# e-programmer-alt.net
KiCad netlist of a schematic drawn in EAGLE
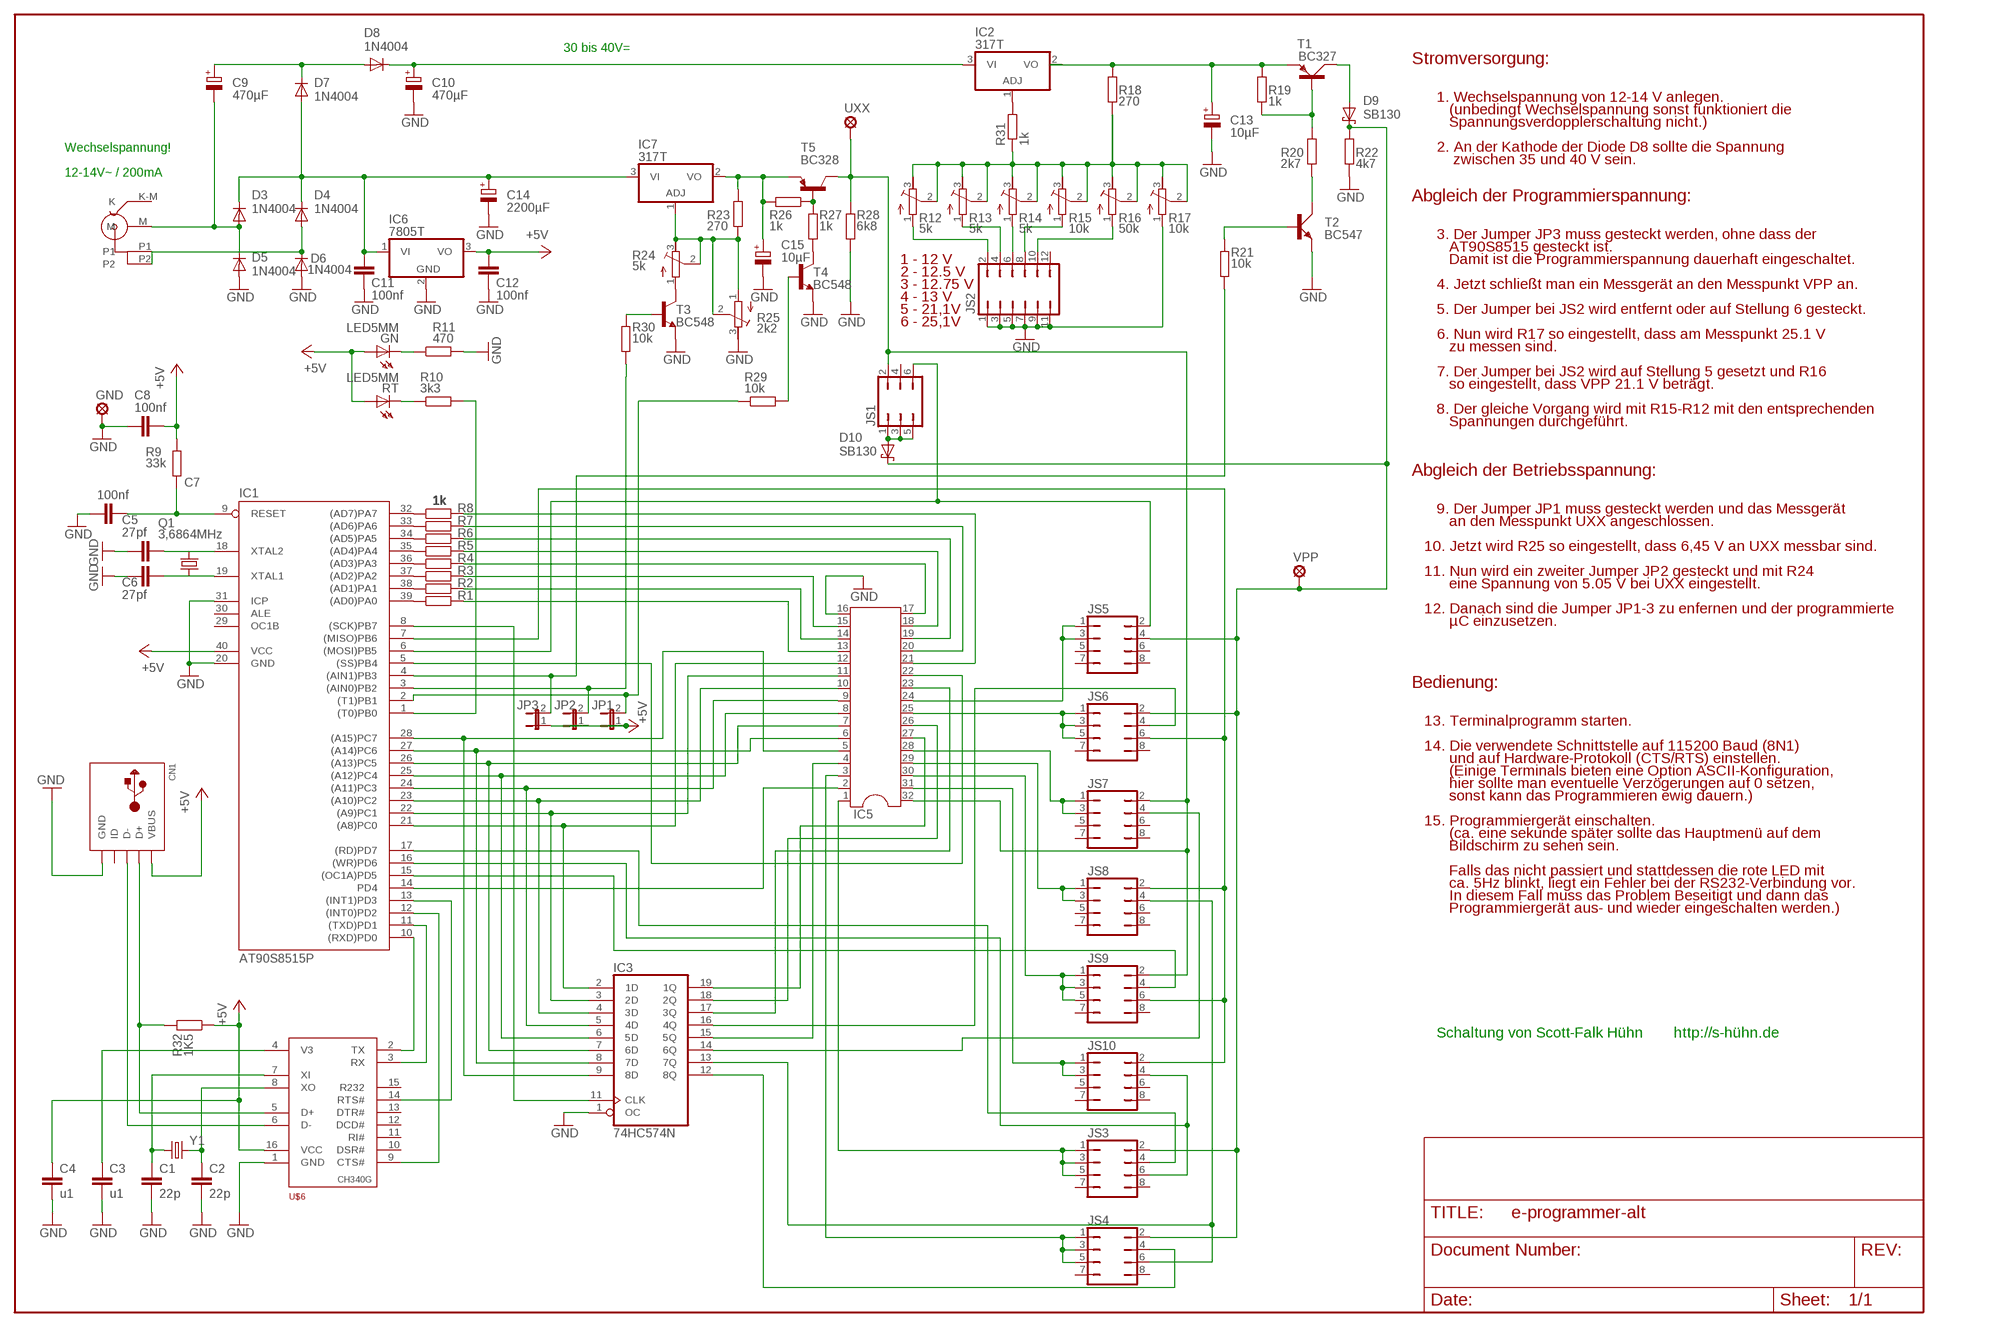
[diagram p0: schematic, sheet 1]

(export (version "E")
  (design (tool "Eeschema 10.0.6"))
  (components
    (comp (ref "BU1")
      (value "KLIN_BU")
      (footprint "eagle-import:KLIN_BU")
      (libsource (lib "eagle-import") (part "KLIN_BU"))
    )
    (comp (ref "C1")
      (value "22p")
      (footprint "eagle-import:C025-025X050")
      (libsource (lib "eagle-import") (part "C-EU025-025X050"))
    )
    (comp (ref "C2")
      (value "22p")
      (footprint "eagle-import:C025-025X050")
      (libsource (lib "eagle-import") (part "C-EU025-025X050"))
    )
    (comp (ref "C3")
      (value "u1")
      (footprint "eagle-import:C025-025X050")
      (libsource (lib "eagle-import") (part "C-EU025-025X050"))
    )
    (comp (ref "C4")
      (value "u1")
      (footprint "eagle-import:C025-025X050")
      (libsource (lib "eagle-import") (part "C-EU025-025X050"))
    )
    (comp (ref "C5")
      (value "27pf")
      (footprint "eagle-import:C025-024X044")
      (libsource (lib "eagle-import") (part "C-EU025-024X044"))
    )
    (comp (ref "C6")
      (value "27pf")
      (footprint "eagle-import:C025-024X044")
      (libsource (lib "eagle-import") (part "C-EU025-024X044"))
    )
    (comp (ref "C7")
      (value "100nf")
      (footprint "eagle-import:C025-024X044")
      (libsource (lib "eagle-import") (part "C-EU025-024X044"))
    )
    (comp (ref "C8")
      (value "100nf")
      (footprint "eagle-import:C025-024X044")
      (libsource (lib "eagle-import") (part "C-EU025-024X044"))
    )
    (comp (ref "C9")
      (value "470µF")
      (footprint "eagle-import:E3,5-10")
      (libsource (lib "eagle-import") (part "CPOL-EUE3.5-10"))
    )
    (comp (ref "C10")
      (value "470µF")
      (footprint "eagle-import:E5-13")
      (libsource (lib "eagle-import") (part "CPOL-EUE5-13"))
    )
    (comp (ref "C11")
      (value "100nf")
      (footprint "eagle-import:C025-024X044")
      (libsource (lib "eagle-import") (part "C-EU025-024X044"))
    )
    (comp (ref "C12")
      (value "100nf")
      (footprint "eagle-import:C025-024X044")
      (libsource (lib "eagle-import") (part "C-EU025-024X044"))
    )
    (comp (ref "C13")
      (value "10µF")
      (footprint "eagle-import:E2,5-5")
      (libsource (lib "eagle-import") (part "CPOL-EUE2.5-5"))
    )
    (comp (ref "C14")
      (value "2200µF")
      (footprint "eagle-import:E7,5-16")
      (libsource (lib "eagle-import") (part "CPOL-EUE7.5-16"))
    )
    (comp (ref "C15")
      (value "10µF")
      (footprint "eagle-import:E5-5")
      (libsource (lib "eagle-import") (part "CPOL-EUE5-5"))
    )
    (comp (ref "CN1")
      (value "USBTHM")
      (footprint "eagle-import:USB-MINIB-THM")
      (libsource (lib "eagle-import") (part "USBTHM"))
    )
    (comp (ref "D3")
      (value "1N4004")
      (footprint "eagle-import:DO41-10")
      (libsource (lib "eagle-import") (part "1N4004"))
    )
    (comp (ref "D4")
      (value "1N4004")
      (footprint "eagle-import:DO41-10")
      (libsource (lib "eagle-import") (part "1N4004"))
    )
    (comp (ref "D5")
      (value "1N4004")
      (footprint "eagle-import:DO41-10")
      (libsource (lib "eagle-import") (part "1N4004"))
    )
    (comp (ref "D6")
      (value "1N4004")
      (footprint "eagle-import:DO41-10")
      (libsource (lib "eagle-import") (part "1N4004"))
    )
    (comp (ref "D7")
      (value "1N4004")
      (footprint "eagle-import:DO41-10")
      (libsource (lib "eagle-import") (part "1N4004"))
    )
    (comp (ref "D8")
      (value "1N4004")
      (footprint "eagle-import:DO41-10")
      (libsource (lib "eagle-import") (part "1N4004"))
    )
    (comp (ref "D9")
      (value "SB130")
      (footprint "eagle-import:DO35-7")
      (libsource (lib "eagle-import") (part "SCHOTTKY-DIODEDO35-7"))
    )
    (comp (ref "D10")
      (value "SB130")
      (footprint "eagle-import:DO35-7")
      (libsource (lib "eagle-import") (part "SCHOTTKY-DIODEDO35-7"))
    )
    (comp (ref "GN")
      (value "LED5MM")
      (footprint "eagle-import:LED5MM")
      (libsource (lib "eagle-import") (part "LED5MM"))
    )
    (comp (ref "GND")
      (value "LSP10")
      (footprint "eagle-import:LSP10")
      (libsource (lib "eagle-import") (part "LSP10"))
    )
    (comp (ref "IC1")
      (value "AT90S8515P")
      (footprint "eagle-import:DIL40")
      (libsource (lib "eagle-import") (part "AT90S8515P"))
    )
    (comp (ref "IC2")
      (value "317T")
      (footprint "eagle-import:TO220H")
      (libsource (lib "eagle-import") (part "317T"))
    )
    (comp (ref "IC3")
      (value "74HC574N")
      (footprint "eagle-import:DIL20")
      (libsource (lib "eagle-import") (part "74574NHC"))
    )
    (comp (ref "IC5")
      (value "DIL32")
      (footprint "eagle-import:DIL32")
      (libsource (lib "eagle-import") (part "DIL32"))
    )
    (comp (ref "IC6")
      (value "7805T")
      (footprint "eagle-import:TO220H")
      (libsource (lib "eagle-import") (part "78T05"))
    )
    (comp (ref "IC7")
      (value "317T")
      (footprint "eagle-import:TO220H")
      (libsource (lib "eagle-import") (part "317T"))
    )
    (comp (ref "JP1")
      (value "JP1E")
      (footprint "eagle-import:JP1")
      (libsource (lib "eagle-import") (part "JP1E"))
    )
    (comp (ref "JP2")
      (value "JP1E")
      (footprint "eagle-import:JP1")
      (libsource (lib "eagle-import") (part "JP1E"))
    )
    (comp (ref "JP3")
      (value "JP1E")
      (footprint "eagle-import:JP1")
      (libsource (lib "eagle-import") (part "JP1E"))
    )
    (comp (ref "JS1")
      (value "JP3Q")
      (footprint "eagle-import:JP3Q")
      (libsource (lib "eagle-import") (part "JP3Q"))
    )
    (comp (ref "JS2")
      (value "JP6Q")
      (footprint "eagle-import:JP6Q")
      (libsource (lib "eagle-import") (part "JP6Q"))
    )
    (comp (ref "JS3")
      (value "JP4Q")
      (footprint "eagle-import:JP4Q")
      (libsource (lib "eagle-import") (part "JP4Q"))
    )
    (comp (ref "JS4")
      (value "JP4Q")
      (footprint "eagle-import:JP4Q")
      (libsource (lib "eagle-import") (part "JP4Q"))
    )
    (comp (ref "JS5")
      (value "JP4Q")
      (footprint "eagle-import:JP4Q")
      (libsource (lib "eagle-import") (part "JP4Q"))
    )
    (comp (ref "JS6")
      (value "JP4Q")
      (footprint "eagle-import:JP4Q")
      (libsource (lib "eagle-import") (part "JP4Q"))
    )
    (comp (ref "JS7")
      (value "JP4Q")
      (footprint "eagle-import:JP4Q")
      (libsource (lib "eagle-import") (part "JP4Q"))
    )
    (comp (ref "JS8")
      (value "JP4Q")
      (footprint "eagle-import:JP4Q")
      (libsource (lib "eagle-import") (part "JP4Q"))
    )
    (comp (ref "JS9")
      (value "JP4Q")
      (footprint "eagle-import:JP4Q")
      (libsource (lib "eagle-import") (part "JP4Q"))
    )
    (comp (ref "JS10")
      (value "JP4Q")
      (footprint "eagle-import:JP4Q")
      (libsource (lib "eagle-import") (part "JP4Q"))
    )
    (comp (ref "Q1")
      (value "3,6864MHz")
      (footprint "eagle-import:HC49U-V")
      (libsource (lib "eagle-import") (part "HC49U-V"))
    )
    (comp (ref "R1")
      (value "1k")
      (footprint "eagle-import:0207_7")
      (libsource (lib "eagle-import") (part "R-EU_0207/7"))
    )
    (comp (ref "R2")
      (value "1k")
      (footprint "eagle-import:0207_7")
      (libsource (lib "eagle-import") (part "R-EU_0207/7"))
    )
    (comp (ref "R3")
      (value "1k")
      (footprint "eagle-import:0207_7")
      (libsource (lib "eagle-import") (part "R-EU_0207/7"))
    )
    (comp (ref "R4")
      (value "1k")
      (footprint "eagle-import:0207_7")
      (libsource (lib "eagle-import") (part "R-EU_0207/7"))
    )
    (comp (ref "R5")
      (value "1k")
      (footprint "eagle-import:0207_7")
      (libsource (lib "eagle-import") (part "R-EU_0207/7"))
    )
    (comp (ref "R6")
      (value "1k")
      (footprint "eagle-import:0207_7")
      (libsource (lib "eagle-import") (part "R-EU_0207/7"))
    )
    (comp (ref "R7")
      (value "1k")
      (footprint "eagle-import:0207_7")
      (libsource (lib "eagle-import") (part "R-EU_0207/7"))
    )
    (comp (ref "R8")
      (value "1k")
      (footprint "eagle-import:0207_7")
      (libsource (lib "eagle-import") (part "R-EU_0207/7"))
    )
    (comp (ref "R9")
      (value "33k")
      (footprint "eagle-import:0204_7")
      (libsource (lib "eagle-import") (part "R-EU_0204/7"))
    )
    (comp (ref "R10")
      (value "3k3")
      (footprint "eagle-import:0204_7")
      (libsource (lib "eagle-import") (part "R-EU_0204/7"))
    )
    (comp (ref "R11")
      (value "470")
      (footprint "eagle-import:0204_7")
      (libsource (lib "eagle-import") (part "R-EU_0204/7"))
    )
    (comp (ref "R12")
      (value "5k")
      (footprint "eagle-import:RTRIM3296Y")
      (libsource (lib "eagle-import") (part "R-TRIMM3296Y"))
    )
    (comp (ref "R13")
      (value "5k")
      (footprint "eagle-import:RTRIM3296Y")
      (libsource (lib "eagle-import") (part "R-TRIMM3296Y"))
    )
    (comp (ref "R14")
      (value "5k")
      (footprint "eagle-import:RTRIM3296Y")
      (libsource (lib "eagle-import") (part "R-TRIMM3296Y"))
    )
    (comp (ref "R15")
      (value "10k")
      (footprint "eagle-import:RTRIM3296Y")
      (libsource (lib "eagle-import") (part "R-TRIMM3296Y"))
    )
    (comp (ref "R16")
      (value "50k")
      (footprint "eagle-import:RTRIM3296Y")
      (libsource (lib "eagle-import") (part "R-TRIMM3296Y"))
    )
    (comp (ref "R17")
      (value "10k")
      (footprint "eagle-import:RTRIM3296Y")
      (libsource (lib "eagle-import") (part "R-TRIMM3296Y"))
    )
    (comp (ref "R18")
      (value "270")
      (footprint "eagle-import:0207_7")
      (libsource (lib "eagle-import") (part "R-EU_0207/7"))
    )
    (comp (ref "R19")
      (value "1k")
      (footprint "eagle-import:0207_7")
      (libsource (lib "eagle-import") (part "R-EU_0207/7"))
    )
    (comp (ref "R20")
      (value "2k7")
      (footprint "eagle-import:0207_7")
      (libsource (lib "eagle-import") (part "R-EU_0207/7"))
    )
    (comp (ref "R21")
      (value "10k")
      (footprint "eagle-import:0207_7")
      (libsource (lib "eagle-import") (part "R-EU_0207/7"))
    )
    (comp (ref "R22")
      (value "4k7")
      (footprint "eagle-import:0207_7")
      (libsource (lib "eagle-import") (part "R-EU_0207/7"))
    )
    (comp (ref "R23")
      (value "270")
      (footprint "eagle-import:0207_7")
      (libsource (lib "eagle-import") (part "R-EU_0207/7"))
    )
    (comp (ref "R24")
      (value "5k")
      (footprint "eagle-import:RTRIM3296Y")
      (libsource (lib "eagle-import") (part "R-TRIMM3296Y"))
    )
    (comp (ref "R25")
      (value "2k2")
      (footprint "eagle-import:RTRIM3296Y")
      (libsource (lib "eagle-import") (part "R-TRIMM3296Y"))
    )
    (comp (ref "R26")
      (value "1k")
      (footprint "eagle-import:0207_7")
      (libsource (lib "eagle-import") (part "R-EU_0207/7"))
    )
    (comp (ref "R27")
      (value "1k")
      (footprint "eagle-import:0207_7")
      (libsource (lib "eagle-import") (part "R-EU_0207/7"))
    )
    (comp (ref "R28")
      (value "6k8")
      (footprint "eagle-import:0207_7")
      (libsource (lib "eagle-import") (part "R-EU_0207/7"))
    )
    (comp (ref "R29")
      (value "10k")
      (footprint "eagle-import:0207_7")
      (libsource (lib "eagle-import") (part "R-EU_0207/7"))
    )
    (comp (ref "R30")
      (value "10k")
      (footprint "eagle-import:0207_7")
      (libsource (lib "eagle-import") (part "R-EU_0207/7"))
    )
    (comp (ref "R31")
      (value "1k")
      (footprint "eagle-import:0207_7")
      (libsource (lib "eagle-import") (part "R-EU_0207/7"))
    )
    (comp (ref "R32")
      (value "1K5")
      (footprint "eagle-import:0204_7")
      (libsource (lib "eagle-import") (part "R-EU_0204/7"))
    )
    (comp (ref "RT")
      (value "LED5MM")
      (footprint "eagle-import:LED5MM")
      (libsource (lib "eagle-import") (part "LED5MM"))
    )
    (comp (ref "T1")
      (value "BC327")
      (footprint "eagle-import:SOT54A")
      (libsource (lib "eagle-import") (part "transistor-small-signal_BC327"))
    )
    (comp (ref "T2")
      (value "BC547")
      (footprint "eagle-import:SOT54A")
      (libsource (lib "eagle-import") (part "transistor-small-signal_BC547"))
    )
    (comp (ref "T3")
      (value "BC548")
      (footprint "eagle-import:TO92")
      (libsource (lib "eagle-import") (part "BC547"))
    )
    (comp (ref "T4")
      (value "BC548")
      (footprint "eagle-import:TO92")
      (libsource (lib "eagle-import") (part "BC547"))
    )
    (comp (ref "T5")
      (value "BC328")
      (footprint "eagle-import:TO92")
      (libsource (lib "eagle-import") (part "BC327"))
    )
    (comp (ref "U$6")
      (value "CH340G")
      (footprint "eagle-import:SO16")
      (libsource (lib "eagle-import") (part "CH340G"))
    )
    (comp (ref "UXX")
      (value "LSP10")
      (footprint "eagle-import:LSP10")
      (libsource (lib "eagle-import") (part "LSP10"))
    )
    (comp (ref "VPP")
      (value "LSP10")
      (footprint "eagle-import:LSP10")
      (libsource (lib "eagle-import") (part "LSP10"))
    )
    (comp (ref "Y1")
      (value "CRYSTALHC49US")
      (footprint "eagle-import:HC49US")
      (libsource (lib "eagle-import") (part "CRYSTALHC49US"))
    )
  )
  (nets
    (net (code "1") (name "+5V") (class "Default")
      (node (ref "C12") (pin "1") (pinfunction "1_1") (pintype "passive"))
      (node (ref "C4") (pin "1") (pinfunction "1_1") (pintype "passive"))
      (node (ref "C8") (pin "2") (pinfunction "2_2") (pintype "passive"))
      (node (ref "CN1") (pin "VBUS") (pinfunction "VBUS_VBUS") (pintype "power_in"))
      (node (ref "GN") (pin "A") (pinfunction "A_A") (pintype "passive"))
      (node (ref "IC1") (pin "40") (pinfunction "VCC_40") (pintype "power_in"))
      (node (ref "IC6") (pin "3") (pinfunction "VO_3") (pintype "passive"))
      (node (ref "JP1") (pin "1") (pinfunction "1_1") (pintype "passive"))
      (node (ref "JP2") (pin "1") (pinfunction "1_1") (pintype "passive"))
      (node (ref "JP3") (pin "1") (pinfunction "1_1") (pintype "passive"))
      (node (ref "R32") (pin "1") (pinfunction "1_1") (pintype "passive"))
      (node (ref "R9") (pin "2") (pinfunction "2_2") (pintype "passive"))
      (node (ref "RT") (pin "A") (pinfunction "A_A") (pintype "passive"))
      (node (ref "U$6") (pin "16") (pinfunction "VCC_16") (pintype "bidirectional"))
    )
    (net (code "2") (name "/VCC_5{slash}6") (class "Default")
      (node (ref "IC1") (pin "3") (pinfunction "(AIN0)PB2_3") (pintype "bidirectional"))
      (node (ref "JP2") (pin "2") (pinfunction "2_2") (pintype "passive"))
      (node (ref "R30") (pin "1") (pinfunction "1_1") (pintype "passive"))
    )
    (net (code "3") (name "GND") (class "Default")
      (node (ref "C1") (pin "2") (pinfunction "2_2") (pintype "passive"))
      (node (ref "C10") (pin "-") (pinfunction "-_-") (pintype "passive"))
      (node (ref "C11") (pin "2") (pinfunction "2_2") (pintype "passive"))
      (node (ref "C12") (pin "2") (pinfunction "2_2") (pintype "passive"))
      (node (ref "C13") (pin "-") (pinfunction "-_-") (pintype "passive"))
      (node (ref "C14") (pin "-") (pinfunction "-_-") (pintype "passive"))
      (node (ref "C15") (pin "-") (pinfunction "-_-") (pintype "passive"))
      (node (ref "C2") (pin "2") (pinfunction "2_2") (pintype "passive"))
      (node (ref "C3") (pin "2") (pinfunction "2_2") (pintype "passive"))
      (node (ref "C4") (pin "2") (pinfunction "2_2") (pintype "passive"))
      (node (ref "C5") (pin "1") (pinfunction "1_1") (pintype "passive"))
      (node (ref "C6") (pin "1") (pinfunction "1_1") (pintype "passive"))
      (node (ref "C7") (pin "1") (pinfunction "1_1") (pintype "passive"))
      (node (ref "C8") (pin "1") (pinfunction "1_1") (pintype "passive"))
      (node (ref "CN1") (pin "GND") (pinfunction "GND_GND") (pintype "power_in"))
      (node (ref "D5") (pin "A") (pinfunction "A_A") (pintype "passive"))
      (node (ref "D6") (pin "A") (pinfunction "A_A") (pintype "passive"))
      (node (ref "GND") (pin "MP") (pinfunction "MP_MP") (pintype "passive"))
      (node (ref "IC1") (pin "20") (pinfunction "GND_20") (pintype "power_in"))
      (node (ref "IC1") (pin "31") (pinfunction "ICP_31") (pintype "bidirectional"))
      (node (ref "IC3") (pin "1") (pinfunction "OC_1") (pintype "input"))
      (node (ref "IC5") (pin "16") (pinfunction "16_16") (pintype "passive"))
      (node (ref "IC6") (pin "2") (pinfunction "GND_2") (pintype "passive"))
      (node (ref "JS2") (pin "1") (pinfunction "1_1") (pintype "passive"))
      (node (ref "JS2") (pin "11") (pinfunction "11_11") (pintype "passive"))
      (node (ref "JS2") (pin "3") (pinfunction "3_3") (pintype "passive"))
      (node (ref "JS2") (pin "5") (pinfunction "5_5") (pintype "passive"))
      (node (ref "JS2") (pin "7") (pinfunction "7_7") (pintype "passive"))
      (node (ref "JS2") (pin "9") (pinfunction "9_9") (pintype "passive"))
      (node (ref "R11") (pin "2") (pinfunction "2_2") (pintype "passive"))
      (node (ref "R17") (pin "1") (pinfunction "E_1") (pintype "passive"))
      (node (ref "R22") (pin "1") (pinfunction "1_1") (pintype "passive"))
      (node (ref "R25") (pin "3") (pinfunction "A_3") (pintype "passive"))
      (node (ref "R28") (pin "1") (pinfunction "1_1") (pintype "passive"))
      (node (ref "T2") (pin "E") (pinfunction "E_E") (pintype "passive"))
      (node (ref "T3") (pin "1") (pinfunction "E_1") (pintype "passive"))
      (node (ref "T4") (pin "1") (pinfunction "E_1") (pintype "passive"))
      (node (ref "U$6") (pin "1") (pinfunction "GND_1") (pintype "bidirectional"))
    )
    (net (code "4") (name "Net-(BU1-PadM)") (class "Default")
      (node (ref "BU1") (pin "M") (pinfunction "M_M") (pintype "bidirectional"))
      (node (ref "C9") (pin "-") (pinfunction "-_-") (pintype "passive"))
      (node (ref "D3") (pin "A") (pinfunction "A_A") (pintype "passive"))
      (node (ref "D5") (pin "C") (pinfunction "C_C") (pintype "passive"))
    )
    (net (code "5") (name "Net-(BU1-PadP1)") (class "Default")
      (node (ref "BU1") (pin "P1") (pinfunction "P1_P1") (pintype "bidirectional"))
      (node (ref "BU1") (pin "P2") (pinfunction "P2_P2") (pintype "bidirectional"))
      (node (ref "D4") (pin "A") (pinfunction "A_A") (pintype "passive"))
      (node (ref "D6") (pin "C") (pinfunction "C_C") (pintype "passive"))
    )
    (net (code "6") (name "Net-(C9-Pad+)") (class "Default")
      (node (ref "C9") (pin "+") (pinfunction "+_+") (pintype "passive"))
      (node (ref "D7") (pin "C") (pinfunction "C_C") (pintype "passive"))
      (node (ref "D8") (pin "A") (pinfunction "A_A") (pintype "passive"))
    )
    (net (code "7") (name "Net-(D9-PadA)") (class "Default")
      (node (ref "D9") (pin "A") (pinfunction "A_A") (pintype "passive"))
      (node (ref "T1") (pin "C") (pinfunction "C_C") (pintype "passive"))
    )
    (net (code "8") (name "Net-(D10-PadA)") (class "Default")
      (node (ref "D10") (pin "A") (pinfunction "A_A") (pintype "passive"))
      (node (ref "JS1") (pin "1") (pinfunction "1_1") (pintype "passive"))
      (node (ref "JS1") (pin "3") (pinfunction "3_3") (pintype "passive"))
      (node (ref "JS1") (pin "5") (pinfunction "5_5") (pintype "passive"))
    )
    (net (code "9") (name "Net-(D10-PadC)") (class "Default")
      (node (ref "D10") (pin "C") (pinfunction "C_C") (pintype "passive"))
      (node (ref "D9") (pin "C") (pinfunction "C_C") (pintype "passive"))
      (node (ref "JS3") (pin "2") (pinfunction "2_2") (pintype "passive"))
      (node (ref "JS4") (pin "2") (pinfunction "2_2") (pintype "passive"))
      (node (ref "JS5") (pin "4") (pinfunction "4_4") (pintype "passive"))
      (node (ref "JS6") (pin "2") (pinfunction "2_2") (pintype "passive"))
      (node (ref "R22") (pin "2") (pinfunction "2_2") (pintype "passive"))
      (node (ref "VPP") (pin "MP") (pinfunction "MP_MP") (pintype "passive"))
    )
    (net (code "10") (name "Net-(GN-C)") (class "Default")
      (node (ref "GN") (pin "K") (pinfunction "C_K") (pintype "passive"))
      (node (ref "R11") (pin "1") (pinfunction "1_1") (pintype "passive"))
    )
    (net (code "11") (name "Net-(IC1-(A8)PC0)") (class "Default")
      (node (ref "IC1") (pin "21") (pinfunction "(A8)PC0_21") (pintype "bidirectional"))
      (node (ref "IC3") (pin "2") (pinfunction "1D_2") (pintype "input"))
      (node (ref "IC5") (pin "12") (pinfunction "12_12") (pintype "passive"))
    )
    (net (code "12") (name "Net-(IC1-(A9)PC1)") (class "Default")
      (node (ref "IC1") (pin "22") (pinfunction "(A9)PC1_22") (pintype "bidirectional"))
      (node (ref "IC3") (pin "3") (pinfunction "2D_3") (pintype "input"))
      (node (ref "IC5") (pin "11") (pinfunction "11_11") (pintype "passive"))
    )
    (net (code "13") (name "Net-(IC1-(A10)PC2)") (class "Default")
      (node (ref "IC1") (pin "23") (pinfunction "(A10)PC2_23") (pintype "bidirectional"))
      (node (ref "IC3") (pin "4") (pinfunction "3D_4") (pintype "input"))
      (node (ref "IC5") (pin "10") (pinfunction "10_10") (pintype "passive"))
    )
    (net (code "14") (name "Net-(IC1-(A11)PC3)") (class "Default")
      (node (ref "IC1") (pin "24") (pinfunction "(A11)PC3_24") (pintype "bidirectional"))
      (node (ref "IC3") (pin "5") (pinfunction "4D_5") (pintype "input"))
      (node (ref "IC5") (pin "9") (pinfunction "9_9") (pintype "passive"))
    )
    (net (code "15") (name "Net-(IC1-(A12)PC4)") (class "Default")
      (node (ref "IC1") (pin "25") (pinfunction "(A12)PC4_25") (pintype "bidirectional"))
      (node (ref "IC3") (pin "6") (pinfunction "5D_6") (pintype "input"))
      (node (ref "IC5") (pin "8") (pinfunction "8_8") (pintype "passive"))
    )
    (net (code "16") (name "Net-(IC1-(A13)PC5)") (class "Default")
      (node (ref "IC1") (pin "26") (pinfunction "(A13)PC5_26") (pintype "bidirectional"))
      (node (ref "IC3") (pin "7") (pinfunction "6D_7") (pintype "input"))
      (node (ref "IC5") (pin "7") (pinfunction "7_7") (pintype "passive"))
    )
    (net (code "17") (name "Net-(IC1-(A14)PC6)") (class "Default")
      (node (ref "IC1") (pin "27") (pinfunction "(A14)PC6_27") (pintype "bidirectional"))
      (node (ref "IC3") (pin "8") (pinfunction "7D_8") (pintype "input"))
      (node (ref "IC5") (pin "6") (pinfunction "6_6") (pintype "passive"))
    )
    (net (code "18") (name "Net-(IC1-(A15)PC7)") (class "Default")
      (node (ref "IC1") (pin "28") (pinfunction "(A15)PC7_28") (pintype "bidirectional"))
      (node (ref "IC3") (pin "9") (pinfunction "8D_9") (pintype "input"))
      (node (ref "IC5") (pin "5") (pinfunction "5_5") (pintype "passive"))
    )
    (net (code "19") (name "Net-(IC1-(AD0)PA0)") (class "Default")
      (node (ref "IC1") (pin "39") (pinfunction "(AD0)PA0_39") (pintype "bidirectional"))
      (node (ref "R1") (pin "1") (pinfunction "1_1") (pintype "passive"))
    )
    (net (code "20") (name "Net-(IC1-(AD1)PA1)") (class "Default")
      (node (ref "IC1") (pin "38") (pinfunction "(AD1)PA1_38") (pintype "bidirectional"))
      (node (ref "R2") (pin "1") (pinfunction "1_1") (pintype "passive"))
    )
    (net (code "21") (name "Net-(IC1-(AD2)PA2)") (class "Default")
      (node (ref "IC1") (pin "37") (pinfunction "(AD2)PA2_37") (pintype "bidirectional"))
      (node (ref "R3") (pin "1") (pinfunction "1_1") (pintype "passive"))
    )
    (net (code "22") (name "Net-(IC1-(AD3)PA3)") (class "Default")
      (node (ref "IC1") (pin "36") (pinfunction "(AD3)PA3_36") (pintype "bidirectional"))
      (node (ref "R4") (pin "1") (pinfunction "1_1") (pintype "passive"))
    )
    (net (code "23") (name "Net-(IC1-(AD4)PA4)") (class "Default")
      (node (ref "IC1") (pin "35") (pinfunction "(AD4)PA4_35") (pintype "bidirectional"))
      (node (ref "R5") (pin "1") (pinfunction "1_1") (pintype "passive"))
    )
    (net (code "24") (name "Net-(IC1-(AD5)PA5)") (class "Default")
      (node (ref "IC1") (pin "34") (pinfunction "(AD5)PA5_34") (pintype "bidirectional"))
      (node (ref "R6") (pin "1") (pinfunction "1_1") (pintype "passive"))
    )
    (net (code "25") (name "Net-(IC1-(AD6)PA6)") (class "Default")
      (node (ref "IC1") (pin "33") (pinfunction "(AD6)PA6_33") (pintype "bidirectional"))
      (node (ref "R7") (pin "1") (pinfunction "1_1") (pintype "passive"))
    )
    (net (code "26") (name "Net-(IC1-(AD7)PA7)") (class "Default")
      (node (ref "IC1") (pin "32") (pinfunction "(AD7)PA7_32") (pintype "bidirectional"))
      (node (ref "R8") (pin "1") (pinfunction "1_1") (pintype "passive"))
    )
    (net (code "27") (name "Net-(IC1-(AIN1)PB3)") (class "Default")
      (node (ref "IC1") (pin "4") (pinfunction "(AIN1)PB3_4") (pintype "bidirectional"))
      (node (ref "JP3") (pin "2") (pinfunction "2_2") (pintype "passive"))
      (node (ref "R21") (pin "1") (pinfunction "1_1") (pintype "passive"))
    )
    (net (code "28") (name "Net-(IC1-(INT0)PD2)") (class "Default")
      (node (ref "IC1") (pin "12") (pinfunction "(INT0)PD2_12") (pintype "bidirectional"))
      (node (ref "U$6") (pin "9") (pinfunction "CTS#_9") (pintype "bidirectional"))
    )
    (net (code "29") (name "Net-(IC1-(INT1)PD3)") (class "Default")
      (node (ref "IC1") (pin "13") (pinfunction "(INT1)PD3_13") (pintype "bidirectional"))
      (node (ref "U$6") (pin "14") (pinfunction "RTS#_14") (pintype "bidirectional"))
    )
    (net (code "30") (name "Net-(IC1-(MISO)PB6)") (class "Default")
      (node (ref "IC1") (pin "7") (pinfunction "(MISO)PB6_7") (pintype "bidirectional"))
      (node (ref "JS10") (pin "2") (pinfunction "2_2") (pintype "passive"))
      (node (ref "JS6") (pin "6") (pinfunction "6_6") (pintype "passive"))
      (node (ref "JS8") (pin "2") (pinfunction "2_2") (pintype "passive"))
      (node (ref "JS9") (pin "6") (pinfunction "6_6") (pintype "passive"))
    )
    (net (code "31") (name "Net-(IC1-(MOSI)PB5)") (class "Default")
      (node (ref "IC1") (pin "6") (pinfunction "(MOSI)PB5_6") (pintype "bidirectional"))
      (node (ref "JS1") (pin "6") (pinfunction "6_6") (pintype "passive"))
      (node (ref "JS5") (pin "2") (pinfunction "2_2") (pintype "passive"))
    )
    (net (code "32") (name "Net-(IC1-(OC1A)PD5)") (class "Default")
      (node (ref "IC1") (pin "15") (pinfunction "(OC1A)PD5_15") (pintype "bidirectional"))
      (node (ref "JS9") (pin "4") (pinfunction "4_4") (pintype "passive"))
    )
    (net (code "33") (name "Net-(IC1-(RD)PD7)") (class "Default")
      (node (ref "IC1") (pin "17") (pinfunction "(RD)PD7_17") (pintype "bidirectional"))
      (node (ref "JS3") (pin "4") (pinfunction "4_4") (pintype "passive"))
    )
    (net (code "34") (name "Net-(IC1-(RXD)PD0)") (class "Default")
      (node (ref "IC1") (pin "10") (pinfunction "(RXD)PD0_10") (pintype "bidirectional"))
      (node (ref "U$6") (pin "2") (pinfunction "TX_2") (pintype "bidirectional"))
    )
    (net (code "35") (name "Net-(IC1-(SCK)PB7)") (class "Default")
      (node (ref "IC1") (pin "8") (pinfunction "(SCK)PB7_8") (pintype "bidirectional"))
      (node (ref "IC3") (pin "11") (pinfunction "CLK_11") (pintype "input"))
    )
    (net (code "36") (name "Net-(IC1-(SS)PB4)") (class "Default")
      (node (ref "IC1") (pin "5") (pinfunction "(SS)PB4_5") (pintype "bidirectional"))
      (node (ref "IC5") (pin "22") (pinfunction "22_22") (pintype "passive"))
    )
    (net (code "37") (name "Net-(IC1-(T0)PB0)") (class "Default")
      (node (ref "IC1") (pin "1") (pinfunction "(T0)PB0_1") (pintype "bidirectional"))
      (node (ref "R10") (pin "2") (pinfunction "2_2") (pintype "passive"))
    )
    (net (code "38") (name "Net-(IC1-(T1)PB1)") (class "Default")
      (node (ref "IC1") (pin "2") (pinfunction "(T1)PB1_2") (pintype "bidirectional"))
      (node (ref "JP1") (pin "2") (pinfunction "2_2") (pintype "passive"))
      (node (ref "R29") (pin "1") (pinfunction "1_1") (pintype "passive"))
    )
    (net (code "39") (name "Net-(IC1-(TXD)PD1)") (class "Default")
      (node (ref "IC1") (pin "11") (pinfunction "(TXD)PD1_11") (pintype "bidirectional"))
      (node (ref "U$6") (pin "3") (pinfunction "RX_3") (pintype "bidirectional"))
    )
    (net (code "40") (name "Net-(IC1-(WR)PD6)") (class "Default")
      (node (ref "IC1") (pin "16") (pinfunction "(WR)PD6_16") (pintype "bidirectional"))
      (node (ref "JS10") (pin "4") (pinfunction "4_4") (pintype "passive"))
      (node (ref "JS3") (pin "6") (pinfunction "6_6") (pintype "passive"))
    )
    (net (code "41") (name "Net-(IC1-PD4)") (class "Default")
      (node (ref "IC1") (pin "14") (pinfunction "PD4_14") (pintype "bidirectional"))
      (node (ref "IC5") (pin "2") (pinfunction "2_2") (pintype "passive"))
    )
    (net (code "42") (name "Net-(IC1-RESET)") (class "Default")
      (node (ref "C7") (pin "2") (pinfunction "2_2") (pintype "passive"))
      (node (ref "IC1") (pin "9") (pinfunction "RESET_9") (pintype "input"))
      (node (ref "R9") (pin "1") (pinfunction "1_1") (pintype "passive"))
    )
    (net (code "43") (name "Net-(IC1-XTAL1)") (class "Default")
      (node (ref "C6") (pin "2") (pinfunction "2_2") (pintype "passive"))
      (node (ref "IC1") (pin "19") (pinfunction "XTAL1_19") (pintype "bidirectional"))
      (node (ref "Q1") (pin "1") (pinfunction "1_1") (pintype "passive"))
    )
    (net (code "44") (name "Net-(IC1-XTAL2)") (class "Default")
      (node (ref "C5") (pin "2") (pinfunction "2_2") (pintype "passive"))
      (node (ref "IC1") (pin "18") (pinfunction "XTAL2_18") (pintype "bidirectional"))
      (node (ref "Q1") (pin "2") (pinfunction "2_2") (pintype "passive"))
    )
    (net (code "45") (name "Net-(IC2-ADJ)") (class "Default")
      (node (ref "IC2") (pin "1") (pinfunction "ADJ_1") (pintype "input"))
      (node (ref "R31") (pin "2") (pinfunction "2_2") (pintype "passive"))
    )
    (net (code "46") (name "Net-(IC2-VI)") (class "Default")
      (node (ref "C10") (pin "+") (pinfunction "+_+") (pintype "passive"))
      (node (ref "D8") (pin "C") (pinfunction "C_C") (pintype "passive"))
      (node (ref "IC2") (pin "3") (pinfunction "VI_3") (pintype "input"))
    )
    (net (code "47") (name "Net-(IC2-VO)") (class "Default")
      (node (ref "C13") (pin "+") (pinfunction "+_+") (pintype "passive"))
      (node (ref "IC2") (pin "2") (pinfunction "VO_2") (pintype "passive"))
      (node (ref "R18") (pin "2") (pinfunction "2_2") (pintype "passive"))
      (node (ref "R19") (pin "2") (pinfunction "2_2") (pintype "passive"))
      (node (ref "T1") (pin "E") (pinfunction "E_E") (pintype "passive"))
    )
    (net (code "48") (name "Net-(IC3A-1Q)") (class "Default")
      (node (ref "IC3") (pin "19") (pinfunction "1Q_19") (pintype "tri_state"))
      (node (ref "IC5") (pin "27") (pinfunction "27_27") (pintype "passive"))
    )
    (net (code "49") (name "Net-(IC3A-2Q)") (class "Default")
      (node (ref "IC3") (pin "18") (pinfunction "2Q_18") (pintype "tri_state"))
      (node (ref "IC5") (pin "26") (pinfunction "26_26") (pintype "passive"))
    )
    (net (code "50") (name "Net-(IC3A-3Q)") (class "Default")
      (node (ref "IC3") (pin "17") (pinfunction "3Q_17") (pintype "tri_state"))
      (node (ref "IC5") (pin "23") (pinfunction "23_23") (pintype "passive"))
    )
    (net (code "51") (name "Net-(IC3A-4Q)") (class "Default")
      (node (ref "IC3") (pin "16") (pinfunction "4Q_16") (pintype "tri_state"))
      (node (ref "JS6") (pin "4") (pinfunction "4_4") (pintype "passive"))
    )
    (net (code "52") (name "Net-(IC3A-5Q)") (class "Default")
      (node (ref "IC3") (pin "15") (pinfunction "5Q_15") (pintype "tri_state"))
      (node (ref "IC5") (pin "4") (pinfunction "4_4") (pintype "passive"))
    )
    (net (code "53") (name "Net-(IC3A-6Q)") (class "Default")
      (node (ref "IC3") (pin "14") (pinfunction "6Q_14") (pintype "tri_state"))
      (node (ref "JS7") (pin "4") (pinfunction "4_4") (pintype "passive"))
    )
    (net (code "54") (name "Net-(IC3A-7Q)") (class "Default")
      (node (ref "IC3") (pin "13") (pinfunction "7Q_13") (pintype "tri_state"))
      (node (ref "JS4") (pin "6") (pinfunction "6_6") (pintype "passive"))
      (node (ref "JS8") (pin "4") (pinfunction "4_4") (pintype "passive"))
    )
    (net (code "55") (name "Net-(IC3A-8Q)") (class "Default")
      (node (ref "IC3") (pin "12") (pinfunction "8Q_12") (pintype "tri_state"))
      (node (ref "JS4") (pin "4") (pinfunction "4_4") (pintype "passive"))
    )
    (net (code "56") (name "Net-(IC5-Pad1)") (class "Default")
      (node (ref "IC5") (pin "1") (pinfunction "1_1") (pintype "passive"))
      (node (ref "JS3") (pin "1") (pinfunction "1_1") (pintype "passive"))
      (node (ref "JS3") (pin "3") (pinfunction "3_3") (pintype "passive"))
      (node (ref "JS3") (pin "5") (pinfunction "5_5") (pintype "passive"))
    )
    (net (code "57") (name "Net-(IC5-Pad3)") (class "Default")
      (node (ref "IC5") (pin "3") (pinfunction "3_3") (pintype "passive"))
      (node (ref "JS4") (pin "1") (pinfunction "1_1") (pintype "passive"))
      (node (ref "JS4") (pin "3") (pinfunction "3_3") (pintype "passive"))
      (node (ref "JS4") (pin "5") (pinfunction "5_5") (pintype "passive"))
    )
    (net (code "58") (name "Net-(IC5-Pad13)") (class "Default")
      (node (ref "IC5") (pin "13") (pinfunction "13_13") (pintype "passive"))
      (node (ref "R1") (pin "2") (pinfunction "2_2") (pintype "passive"))
    )
    (net (code "59") (name "Net-(IC5-Pad14)") (class "Default")
      (node (ref "IC5") (pin "14") (pinfunction "14_14") (pintype "passive"))
      (node (ref "R2") (pin "2") (pinfunction "2_2") (pintype "passive"))
    )
    (net (code "60") (name "Net-(IC5-Pad15)") (class "Default")
      (node (ref "IC5") (pin "15") (pinfunction "15_15") (pintype "passive"))
      (node (ref "R3") (pin "2") (pinfunction "2_2") (pintype "passive"))
    )
    (net (code "61") (name "Net-(IC5-Pad17)") (class "Default")
      (node (ref "IC5") (pin "17") (pinfunction "17_17") (pintype "passive"))
      (node (ref "R4") (pin "2") (pinfunction "2_2") (pintype "passive"))
    )
    (net (code "62") (name "Net-(IC5-Pad18)") (class "Default")
      (node (ref "IC5") (pin "18") (pinfunction "18_18") (pintype "passive"))
      (node (ref "R5") (pin "2") (pinfunction "2_2") (pintype "passive"))
    )
    (net (code "63") (name "Net-(IC5-Pad19)") (class "Default")
      (node (ref "IC5") (pin "19") (pinfunction "19_19") (pintype "passive"))
      (node (ref "R6") (pin "2") (pinfunction "2_2") (pintype "passive"))
    )
    (net (code "64") (name "Net-(IC5-Pad20)") (class "Default")
      (node (ref "IC5") (pin "20") (pinfunction "20_20") (pintype "passive"))
      (node (ref "R7") (pin "2") (pinfunction "2_2") (pintype "passive"))
    )
    (net (code "65") (name "Net-(IC5-Pad21)") (class "Default")
      (node (ref "IC5") (pin "21") (pinfunction "21_21") (pintype "passive"))
      (node (ref "R8") (pin "2") (pinfunction "2_2") (pintype "passive"))
    )
    (net (code "66") (name "Net-(IC5-Pad24)") (class "Default")
      (node (ref "IC5") (pin "24") (pinfunction "24_24") (pintype "passive"))
      (node (ref "JS5") (pin "1") (pinfunction "1_1") (pintype "passive"))
      (node (ref "JS5") (pin "3") (pinfunction "3_3") (pintype "passive"))
    )
    (net (code "67") (name "Net-(IC5-Pad25)") (class "Default")
      (node (ref "IC5") (pin "25") (pinfunction "25_25") (pintype "passive"))
      (node (ref "JS6") (pin "1") (pinfunction "1_1") (pintype "passive"))
      (node (ref "JS6") (pin "3") (pinfunction "3_3") (pintype "passive"))
      (node (ref "JS6") (pin "5") (pinfunction "5_5") (pintype "passive"))
    )
    (net (code "68") (name "Net-(IC5-Pad28)") (class "Default")
      (node (ref "IC5") (pin "28") (pinfunction "28_28") (pintype "passive"))
      (node (ref "JS7") (pin "1") (pinfunction "1_1") (pintype "passive"))
      (node (ref "JS7") (pin "3") (pinfunction "3_3") (pintype "passive"))
    )
    (net (code "69") (name "Net-(IC5-Pad29)") (class "Default")
      (node (ref "IC5") (pin "29") (pinfunction "29_29") (pintype "passive"))
      (node (ref "JS8") (pin "1") (pinfunction "1_1") (pintype "passive"))
      (node (ref "JS8") (pin "3") (pinfunction "3_3") (pintype "passive"))
    )
    (net (code "70") (name "Net-(IC5-Pad30)") (class "Default")
      (node (ref "IC5") (pin "30") (pinfunction "30_30") (pintype "passive"))
      (node (ref "JS9") (pin "1") (pinfunction "1_1") (pintype "passive"))
      (node (ref "JS9") (pin "3") (pinfunction "3_3") (pintype "passive"))
      (node (ref "JS9") (pin "5") (pinfunction "5_5") (pintype "passive"))
    )
    (net (code "71") (name "Net-(IC5-Pad31)") (class "Default")
      (node (ref "IC5") (pin "31") (pinfunction "31_31") (pintype "passive"))
      (node (ref "JS10") (pin "1") (pinfunction "1_1") (pintype "passive"))
      (node (ref "JS10") (pin "3") (pinfunction "3_3") (pintype "passive"))
    )
    (net (code "72") (name "Net-(IC6-VI)") (class "Default")
      (node (ref "C11") (pin "1") (pinfunction "1_1") (pintype "passive"))
      (node (ref "C14") (pin "+") (pinfunction "+_+") (pintype "passive"))
      (node (ref "D3") (pin "C") (pinfunction "C_C") (pintype "passive"))
      (node (ref "D4") (pin "C") (pinfunction "C_C") (pintype "passive"))
      (node (ref "D7") (pin "A") (pinfunction "A_A") (pintype "passive"))
      (node (ref "IC6") (pin "1") (pinfunction "VI_1") (pintype "input"))
      (node (ref "IC7") (pin "3") (pinfunction "VI_3") (pintype "input"))
    )
    (net (code "73") (name "Net-(IC7-ADJ)") (class "Default")
      (node (ref "IC7") (pin "1") (pinfunction "ADJ_1") (pintype "input"))
      (node (ref "R23") (pin "1") (pinfunction "1_1") (pintype "passive"))
      (node (ref "R24") (pin "2") (pinfunction "S_2") (pintype "passive"))
      (node (ref "R24") (pin "3") (pinfunction "A_3") (pintype "passive"))
      (node (ref "R25") (pin "1") (pinfunction "E_1") (pintype "passive"))
      (node (ref "R25") (pin "2") (pinfunction "S_2") (pintype "passive"))
    )
    (net (code "74") (name "Net-(IC7-VO)") (class "Default")
      (node (ref "C15") (pin "+") (pinfunction "+_+") (pintype "passive"))
      (node (ref "IC7") (pin "2") (pinfunction "VO_2") (pintype "passive"))
      (node (ref "R23") (pin "2") (pinfunction "2_2") (pintype "passive"))
      (node (ref "R26") (pin "2") (pinfunction "2_2") (pintype "passive"))
      (node (ref "T5") (pin "1") (pinfunction "E_1") (pintype "passive"))
    )
    (net (code "75") (name "Net-(R12-A)") (class "Default")
      (node (ref "R12") (pin "2") (pinfunction "S_2") (pintype "passive"))
      (node (ref "R12") (pin "3") (pinfunction "A_3") (pintype "passive"))
      (node (ref "R13") (pin "2") (pinfunction "S_2") (pintype "passive"))
      (node (ref "R13") (pin "3") (pinfunction "A_3") (pintype "passive"))
      (node (ref "R14") (pin "2") (pinfunction "S_2") (pintype "passive"))
      (node (ref "R14") (pin "3") (pinfunction "A_3") (pintype "passive"))
      (node (ref "R15") (pin "2") (pinfunction "S_2") (pintype "passive"))
      (node (ref "R15") (pin "3") (pinfunction "A_3") (pintype "passive"))
      (node (ref "R16") (pin "2") (pinfunction "S_2") (pintype "passive"))
      (node (ref "R16") (pin "3") (pinfunction "A_3") (pintype "passive"))
      (node (ref "R17") (pin "2") (pinfunction "S_2") (pintype "passive"))
      (node (ref "R17") (pin "3") (pinfunction "A_3") (pintype "passive"))
      (node (ref "R18") (pin "1") (pinfunction "1_1") (pintype "passive"))
      (node (ref "R31") (pin "1") (pinfunction "1_1") (pintype "passive"))
    )
    (net (code "76") (name "Net-(R12-E)") (class "Default")
      (node (ref "JS2") (pin "2") (pinfunction "2_2") (pintype "passive"))
      (node (ref "R12") (pin "1") (pinfunction "E_1") (pintype "passive"))
    )
    (net (code "77") (name "Net-(R13-E)") (class "Default")
      (node (ref "JS2") (pin "4") (pinfunction "4_4") (pintype "passive"))
      (node (ref "R13") (pin "1") (pinfunction "E_1") (pintype "passive"))
    )
    (net (code "78") (name "Net-(R14-E)") (class "Default")
      (node (ref "JS2") (pin "6") (pinfunction "6_6") (pintype "passive"))
      (node (ref "R14") (pin "1") (pinfunction "E_1") (pintype "passive"))
    )
    (net (code "79") (name "Net-(R15-E)") (class "Default")
      (node (ref "JS2") (pin "8") (pinfunction "8_8") (pintype "passive"))
      (node (ref "R15") (pin "1") (pinfunction "E_1") (pintype "passive"))
    )
    (net (code "80") (name "Net-(R16-E)") (class "Default")
      (node (ref "JS2") (pin "10") (pinfunction "10_10") (pintype "passive"))
      (node (ref "R16") (pin "1") (pinfunction "E_1") (pintype "passive"))
    )
    (net (code "81") (name "Net-(R19-Pad1)") (class "Default")
      (node (ref "R19") (pin "1") (pinfunction "1_1") (pintype "passive"))
      (node (ref "R20") (pin "2") (pinfunction "2_2") (pintype "passive"))
      (node (ref "T1") (pin "B") (pinfunction "B_B") (pintype "passive"))
    )
    (net (code "82") (name "Net-(R20-Pad1)") (class "Default")
      (node (ref "R20") (pin "1") (pinfunction "1_1") (pintype "passive"))
      (node (ref "T2") (pin "C") (pinfunction "C_C") (pintype "passive"))
    )
    (net (code "83") (name "Net-(R21-Pad2)") (class "Default")
      (node (ref "R21") (pin "2") (pinfunction "2_2") (pintype "passive"))
      (node (ref "T2") (pin "B") (pinfunction "B_B") (pintype "passive"))
    )
    (net (code "84") (name "Net-(R24-E)") (class "Default")
      (node (ref "R24") (pin "1") (pinfunction "E_1") (pintype "passive"))
      (node (ref "T3") (pin "3") (pinfunction "C_3") (pintype "passive"))
    )
    (net (code "85") (name "Net-(RT-C)") (class "Default")
      (node (ref "R10") (pin "1") (pinfunction "1_1") (pintype "passive"))
      (node (ref "RT") (pin "K") (pinfunction "C_K") (pintype "passive"))
    )
    (net (code "86") (name "Net-(T3-B)") (class "Default")
      (node (ref "R30") (pin "2") (pinfunction "2_2") (pintype "passive"))
      (node (ref "T3") (pin "2") (pinfunction "B_2") (pintype "passive"))
    )
    (net (code "87") (name "Net-(T4-B)") (class "Default")
      (node (ref "R29") (pin "2") (pinfunction "2_2") (pintype "passive"))
      (node (ref "T4") (pin "2") (pinfunction "B_2") (pintype "passive"))
    )
    (net (code "88") (name "Net-(T4-C)") (class "Default")
      (node (ref "R27") (pin "1") (pinfunction "1_1") (pintype "passive"))
      (node (ref "T4") (pin "3") (pinfunction "C_3") (pintype "passive"))
    )
    (net (code "89") (name "Net-(T5-B)") (class "Default")
      (node (ref "R26") (pin "1") (pinfunction "1_1") (pintype "passive"))
      (node (ref "R27") (pin "2") (pinfunction "2_2") (pintype "passive"))
      (node (ref "T5") (pin "2") (pinfunction "B_2") (pintype "passive"))
    )
    (net (code "90") (name "Net-(T5-C)") (class "Default")
      (node (ref "IC5") (pin "32") (pinfunction "32_32") (pintype "passive"))
      (node (ref "JS1") (pin "2") (pinfunction "2_2") (pintype "passive"))
      (node (ref "JS7") (pin "2") (pinfunction "2_2") (pintype "passive"))
      (node (ref "JS9") (pin "2") (pinfunction "2_2") (pintype "passive"))
      (node (ref "R28") (pin "2") (pinfunction "2_2") (pintype "passive"))
      (node (ref "T5") (pin "3") (pinfunction "C_3") (pintype "passive"))
      (node (ref "UXX") (pin "MP") (pinfunction "MP_MP") (pintype "passive"))
    )
    (net (code "91") (name "Net-(U$6-D+)") (class "Default")
      (node (ref "CN1") (pin "D+") (pinfunction "D+_D+") (pintype "bidirectional"))
      (node (ref "R32") (pin "2") (pinfunction "2_2") (pintype "passive"))
      (node (ref "U$6") (pin "5") (pinfunction "D+_5") (pintype "bidirectional"))
    )
    (net (code "92") (name "Net-(U$6-D-)") (class "Default")
      (node (ref "CN1") (pin "D-") (pinfunction "D-_D-") (pintype "bidirectional"))
      (node (ref "U$6") (pin "6") (pinfunction "D-_6") (pintype "bidirectional"))
    )
    (net (code "93") (name "Net-(U$6-V3)") (class "Default")
      (node (ref "C3") (pin "1") (pinfunction "1_1") (pintype "passive"))
      (node (ref "U$6") (pin "4") (pinfunction "V3_4") (pintype "bidirectional"))
    )
    (net (code "94") (name "Net-(U$6-XI)") (class "Default")
      (node (ref "C1") (pin "1") (pinfunction "1_1") (pintype "passive"))
      (node (ref "U$6") (pin "7") (pinfunction "XI_7") (pintype "bidirectional"))
      (node (ref "Y1") (pin "1") (pinfunction "1_1") (pintype "passive"))
    )
    (net (code "95") (name "Net-(U$6-XO)") (class "Default")
      (node (ref "C2") (pin "1") (pinfunction "1_1") (pintype "passive"))
      (node (ref "U$6") (pin "8") (pinfunction "XO_8") (pintype "bidirectional"))
      (node (ref "Y1") (pin "2") (pinfunction "2_2") (pintype "passive"))
    )
    (net (code "96") (name "unconnected-(BU1-K-PadK-M)") (class "Default")
      (node (ref "BU1") (pin "K-M") (pinfunction "K_K-M") (pintype "bidirectional"))
    )
    (net (code "97") (name "unconnected-(CN1-PadID)") (class "Default")
      (node (ref "CN1") (pin "ID") (pinfunction "ID_ID") (pintype "bidirectional"))
    )
    (net (code "98") (name "unconnected-(IC1-ALE-Pad30)") (class "Default")
      (node (ref "IC1") (pin "30") (pinfunction "ALE_30") (pintype "bidirectional"))
    )
    (net (code "99") (name "unconnected-(IC1-OC1B-Pad29)") (class "Default")
      (node (ref "IC1") (pin "29") (pinfunction "OC1B_29") (pintype "bidirectional"))
    )
    (net (code "100") (name "unconnected-(JS1-Pad4)") (class "Default")
      (node (ref "JS1") (pin "4") (pinfunction "4_4") (pintype "passive"))
    )
    (net (code "101") (name "unconnected-(JS2-Pad12)") (class "Default")
      (node (ref "JS2") (pin "12") (pinfunction "12_12") (pintype "passive"))
    )
    (net (code "102") (name "unconnected-(JS3-Pad7)") (class "Default")
      (node (ref "JS3") (pin "7") (pinfunction "7_7") (pintype "passive"))
    )
    (net (code "103") (name "unconnected-(JS3-Pad8)") (class "Default")
      (node (ref "JS3") (pin "8") (pinfunction "8_8") (pintype "passive"))
    )
    (net (code "104") (name "unconnected-(JS4-Pad7)") (class "Default")
      (node (ref "JS4") (pin "7") (pinfunction "7_7") (pintype "passive"))
    )
    (net (code "105") (name "unconnected-(JS4-Pad8)") (class "Default")
      (node (ref "JS4") (pin "8") (pinfunction "8_8") (pintype "passive"))
    )
    (net (code "106") (name "unconnected-(JS5-Pad5)") (class "Default")
      (node (ref "JS5") (pin "5") (pinfunction "5_5") (pintype "passive"))
    )
    (net (code "107") (name "unconnected-(JS5-Pad6)") (class "Default")
      (node (ref "JS5") (pin "6") (pinfunction "6_6") (pintype "passive"))
    )
    (net (code "108") (name "unconnected-(JS5-Pad7)") (class "Default")
      (node (ref "JS5") (pin "7") (pinfunction "7_7") (pintype "passive"))
    )
    (net (code "109") (name "unconnected-(JS5-Pad8)") (class "Default")
      (node (ref "JS5") (pin "8") (pinfunction "8_8") (pintype "passive"))
    )
    (net (code "110") (name "unconnected-(JS6-Pad7)") (class "Default")
      (node (ref "JS6") (pin "7") (pinfunction "7_7") (pintype "passive"))
    )
    (net (code "111") (name "unconnected-(JS6-Pad8)") (class "Default")
      (node (ref "JS6") (pin "8") (pinfunction "8_8") (pintype "passive"))
    )
    (net (code "112") (name "unconnected-(JS7-Pad5)") (class "Default")
      (node (ref "JS7") (pin "5") (pinfunction "5_5") (pintype "passive"))
    )
    (net (code "113") (name "unconnected-(JS7-Pad6)") (class "Default")
      (node (ref "JS7") (pin "6") (pinfunction "6_6") (pintype "passive"))
    )
    (net (code "114") (name "unconnected-(JS7-Pad7)") (class "Default")
      (node (ref "JS7") (pin "7") (pinfunction "7_7") (pintype "passive"))
    )
    (net (code "115") (name "unconnected-(JS7-Pad8)") (class "Default")
      (node (ref "JS7") (pin "8") (pinfunction "8_8") (pintype "passive"))
    )
    (net (code "116") (name "unconnected-(JS8-Pad5)") (class "Default")
      (node (ref "JS8") (pin "5") (pinfunction "5_5") (pintype "passive"))
    )
    (net (code "117") (name "unconnected-(JS8-Pad6)") (class "Default")
      (node (ref "JS8") (pin "6") (pinfunction "6_6") (pintype "passive"))
    )
    (net (code "118") (name "unconnected-(JS8-Pad7)") (class "Default")
      (node (ref "JS8") (pin "7") (pinfunction "7_7") (pintype "passive"))
    )
    (net (code "119") (name "unconnected-(JS8-Pad8)") (class "Default")
      (node (ref "JS8") (pin "8") (pinfunction "8_8") (pintype "passive"))
    )
    (net (code "120") (name "unconnected-(JS9-Pad7)") (class "Default")
      (node (ref "JS9") (pin "7") (pinfunction "7_7") (pintype "passive"))
    )
    (net (code "121") (name "unconnected-(JS9-Pad8)") (class "Default")
      (node (ref "JS9") (pin "8") (pinfunction "8_8") (pintype "passive"))
    )
    (net (code "122") (name "unconnected-(JS10-Pad5)") (class "Default")
      (node (ref "JS10") (pin "5") (pinfunction "5_5") (pintype "passive"))
    )
    (net (code "123") (name "unconnected-(JS10-Pad6)") (class "Default")
      (node (ref "JS10") (pin "6") (pinfunction "6_6") (pintype "passive"))
    )
    (net (code "124") (name "unconnected-(JS10-Pad7)") (class "Default")
      (node (ref "JS10") (pin "7") (pinfunction "7_7") (pintype "passive"))
    )
    (net (code "125") (name "unconnected-(JS10-Pad8)") (class "Default")
      (node (ref "JS10") (pin "8") (pinfunction "8_8") (pintype "passive"))
    )
    (net (code "126") (name "unconnected-(U$6-DCD#-Pad12)") (class "Default")
      (node (ref "U$6") (pin "12") (pinfunction "DCD#_12") (pintype "bidirectional"))
    )
    (net (code "127") (name "unconnected-(U$6-DSR#-Pad10)") (class "Default")
      (node (ref "U$6") (pin "10") (pinfunction "DSR#_10") (pintype "bidirectional"))
    )
    (net (code "128") (name "unconnected-(U$6-DTR#-Pad13)") (class "Default")
      (node (ref "U$6") (pin "13") (pinfunction "DTR#_13") (pintype "bidirectional"))
    )
    (net (code "129") (name "unconnected-(U$6-R232-Pad15)") (class "Default")
      (node (ref "U$6") (pin "15") (pinfunction "R232_15") (pintype "bidirectional"))
    )
    (net (code "130") (name "unconnected-(U$6-RI#-Pad11)") (class "Default")
      (node (ref "U$6") (pin "11") (pinfunction "RI#_11") (pintype "bidirectional"))
    )
  )
)
